# PCB_Project_Demo.net
KiCad netlist of a schematic drawn in Altium Designer
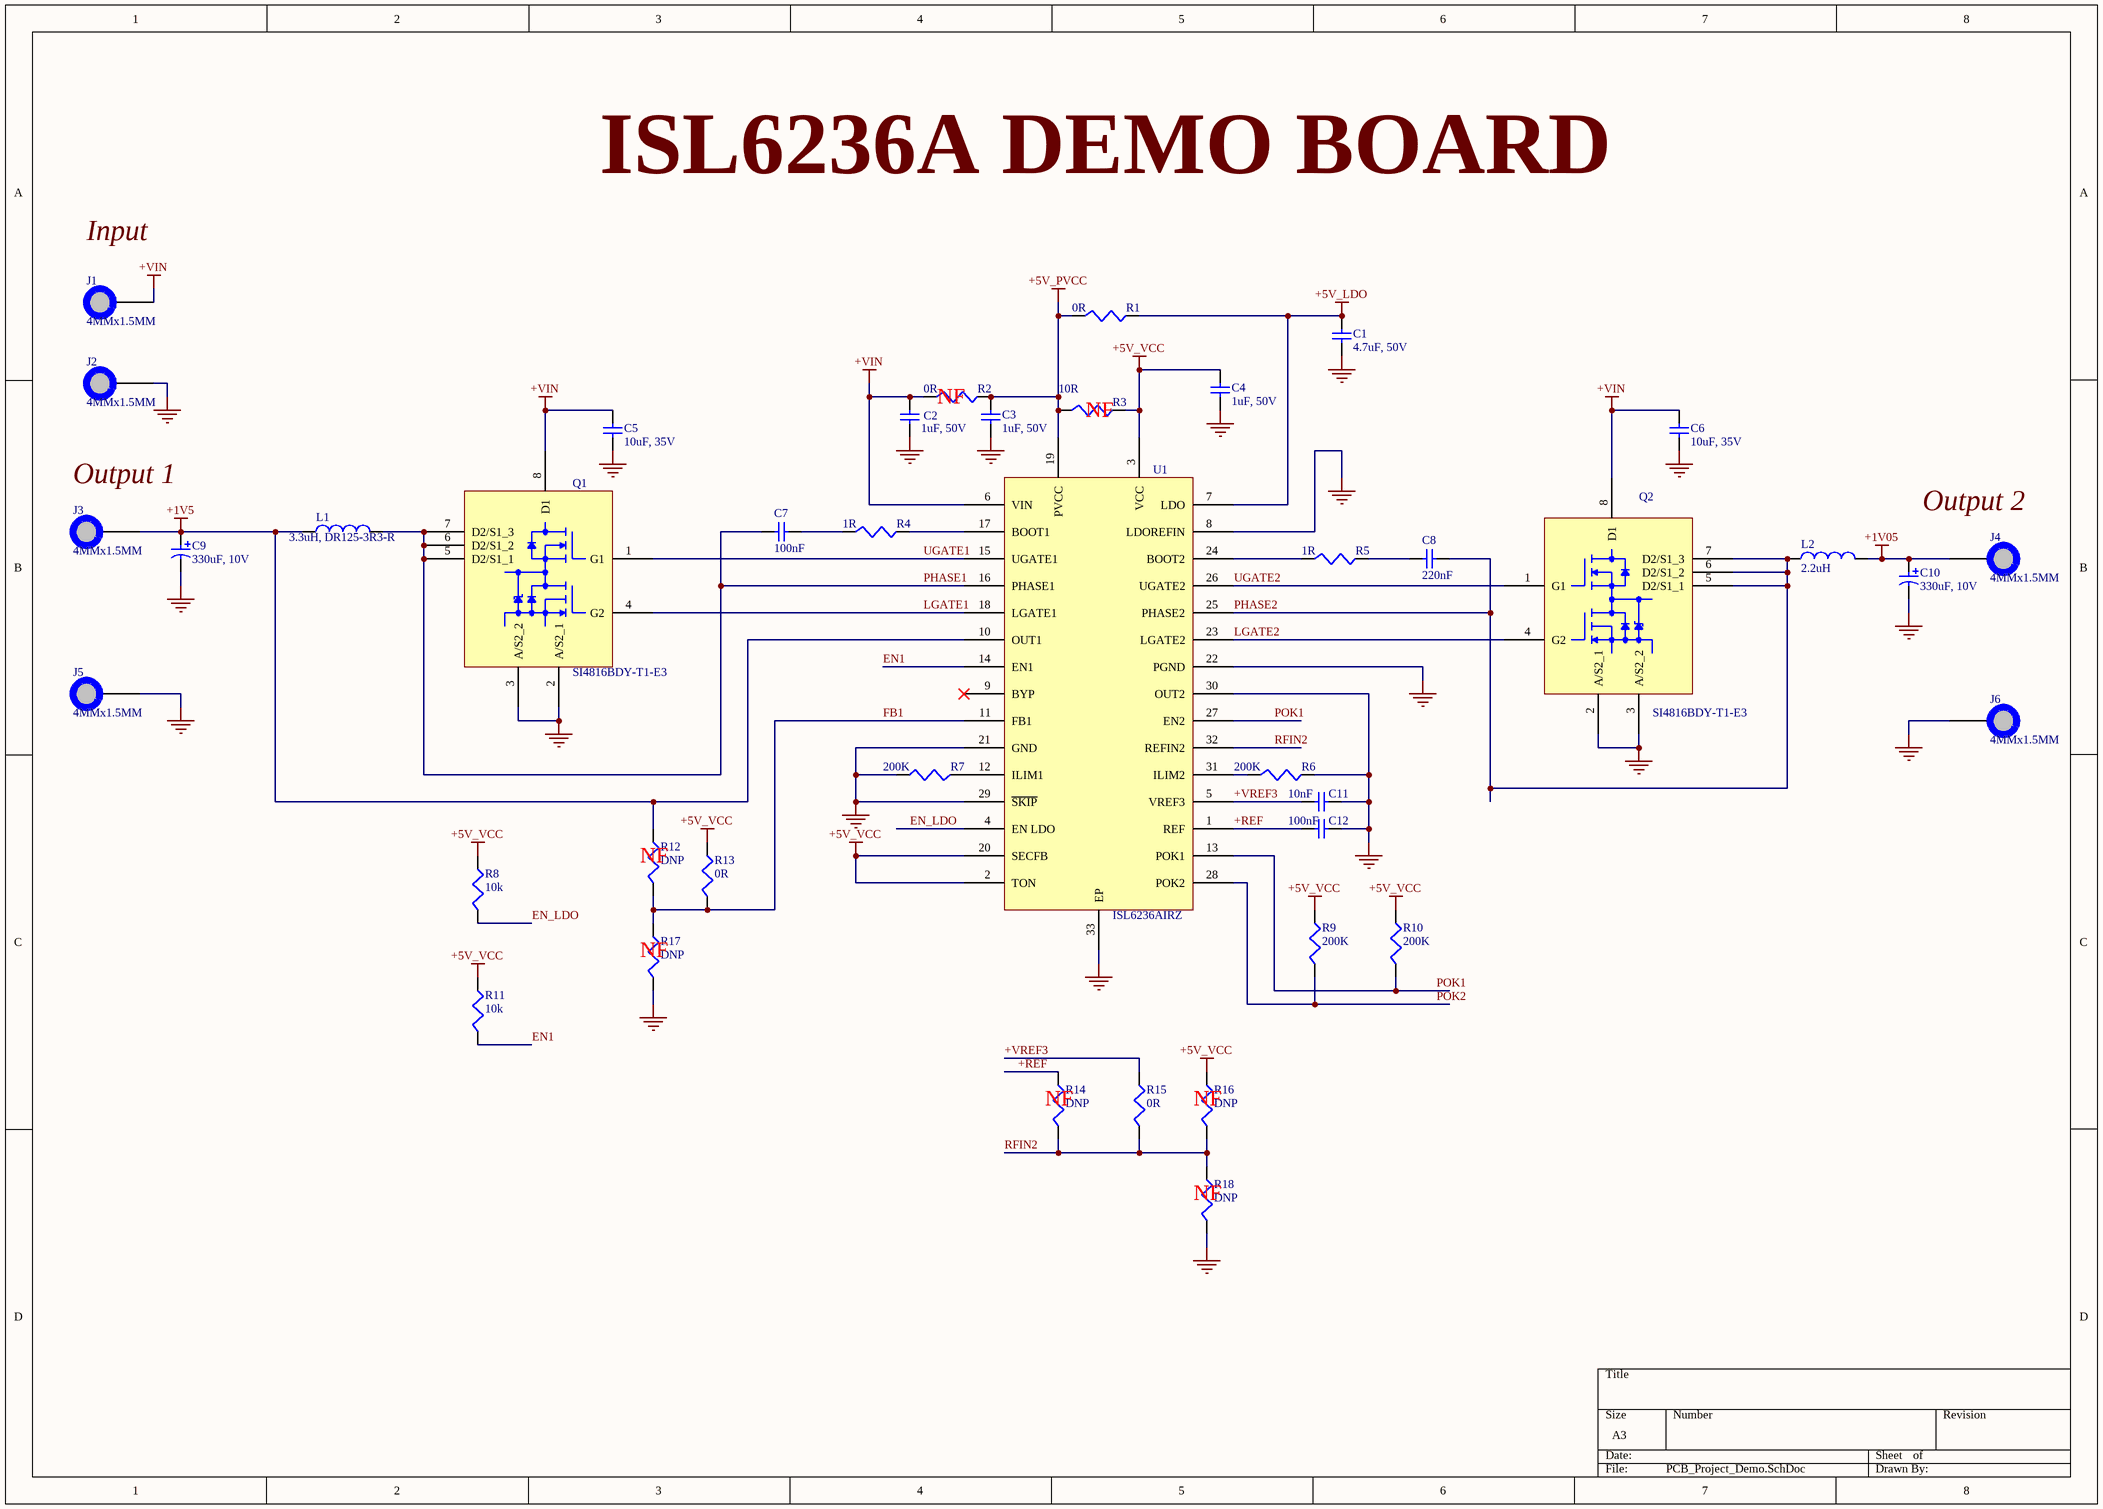
[diagram p0: PCB_Project_Demo.SchDoc]

(export (version "E")
  (design (tool "Eeschema 10.0.6"))
  (components
    (comp (ref "C1")
      (value "4.7uF, 50V")
      (footprint "C1206")
      (fields
        (field (name "MANUFACTURER") "TDK")
        (field (name "MANUFACTURER PART NUMBER") "C3216X5R1H475K160AB")
      )
      (libsource (lib "PCB_Project_Demo") (part "C3216X5R1H475K160AB"))
    )
    (comp (ref "C2")
      (value "1uF, 50V")
      (footprint "C0805")
      (fields
        (field (name "MANUFACTURER") "KEMET")
        (field (name "MANUFACTURER PART NUMBER") "C0805C105K5RACTU")
      )
      (libsource (lib "PCB_Project_Demo") (part "C0805C105K5RACTU (2)"))
    )
    (comp (ref "C3")
      (value "1uF, 50V")
      (footprint "C0805")
      (fields
        (field (name "MANUFACTURER") "KEMET")
        (field (name "MANUFACTURER PART NUMBER") "C0805C105K5RACTU")
      )
      (libsource (lib "PCB_Project_Demo") (part "C0805C105K5RACTU (2)"))
    )
    (comp (ref "C4")
      (value "1uF, 50V")
      (footprint "C0805")
      (fields
        (field (name "MANUFACTURER") "KEMET")
        (field (name "MANUFACTURER PART NUMBER") "C0805C105K5RACTU")
      )
      (libsource (lib "PCB_Project_Demo") (part "C0805C105K5RACTU (2)"))
    )
    (comp (ref "C5")
      (value "10uF, 35V")
      (footprint "C1210")
      (fields
        (field (name "MANUFACTURER") "KEMET")
        (field (name "MANUFACTURER PART NUMBER") "C1210C106K6PACTU")
      )
      (libsource (lib "PCB_Project_Demo") (part "C1210C106K6PACTU"))
    )
    (comp (ref "C6")
      (value "10uF, 35V")
      (footprint "C1210")
      (fields
        (field (name "MANUFACTURER") "KEMET")
        (field (name "MANUFACTURER PART NUMBER") "C1210C106K6PACTU")
      )
      (libsource (lib "PCB_Project_Demo") (part "C1210C106K6PACTU"))
    )
    (comp (ref "C7")
      (value "100nF")
      (footprint "C0805")
      (description "Multilayer Ceramic Capacitor, 0.1 uF, 50 V, ± 10%, X7R, 0805 [2012 Metric]")
      (fields
        (field (name "MANUFACTURER") "KEMET")
        (field (name "MANUFACTURER PART NUMBER") "C0805C104K5RAC7800")
      )
      (libsource (lib "PCB_Project_Demo") (part "C0805C104K5RAC7800"))
    )
    (comp (ref "C8")
      (value "220nF")
      (footprint "C0805")
      (fields
        (field (name "MANUFACTURER") "KEMET")
        (field (name "MANUFACTURER PART NUMBER") "C0805C224K5RACTU")
      )
      (libsource (lib "PCB_Project_Demo") (part "C0805C224K5RACTU"))
    )
    (comp (ref "C9")
      (value "330uF, 10V")
      (footprint "7343-43")
      (fields
        (field (name "MANUFACTURER") "KEMET")
        (field (name "MANUFACTURER PART NUMBER") "T530X337M010ATE004")
      )
      (libsource (lib "PCB_Project_Demo") (part "T530X337M010ATE004"))
    )
    (comp (ref "C10")
      (value "330uF, 10V")
      (footprint "7343-43")
      (fields
        (field (name "MANUFACTURER") "KEMET")
        (field (name "MANUFACTURER PART NUMBER") "T530X337M010ATE004")
      )
      (libsource (lib "PCB_Project_Demo") (part "T530X337M010ATE004"))
    )
    (comp (ref "C11")
      (value "10nF")
      (footprint "C0805")
      (description "Ceramic Capacitor, Ceramic, 50V, 10% +Tol, 10% -Tol, X7R, -/+15ppm/Cel TC, 0.01uF, 0805")
      (fields
        (field (name "MANUFACTURER") "KEMET")
        (field (name "MANUFACTURER PART NUMBER") "C0805F103K5RACTU")
      )
      (libsource (lib "PCB_Project_Demo") (part "C0805F103K5RACTU"))
    )
    (comp (ref "C12")
      (value "100nF")
      (footprint "C0805")
      (description "Multilayer Ceramic Capacitor, 0.1 uF, 50 V, ± 10%, X7R, 0805 [2012 Metric]")
      (fields
        (field (name "MANUFACTURER") "KEMET")
        (field (name "MANUFACTURER PART NUMBER") "C0805C104K5RAC7800")
      )
      (libsource (lib "PCB_Project_Demo") (part "C0805C104K5RAC7800"))
    )
    (comp (ref "J1")
      (value "4MMx1.5MM")
      (footprint "PAD_WITH_HOLE_4MMx1MM5")
      (description "Pad with a hole 4mm x 1.5mm")
      (libsource (lib "PCB_Project_Demo") (part "PAD_WITH_HOLE_4MMx1MM5"))
    )
    (comp (ref "J2")
      (value "4MMx1.5MM")
      (footprint "PAD_WITH_HOLE_4MMx1MM5")
      (description "Pad with a hole 4mm x 1.5mm")
      (libsource (lib "PCB_Project_Demo") (part "PAD_WITH_HOLE_4MMx1MM5"))
    )
    (comp (ref "J3")
      (value "4MMx1.5MM")
      (footprint "PAD_WITH_HOLE_4MMx1MM5")
      (description "Pad with a hole 4mm x 1.5mm")
      (libsource (lib "PCB_Project_Demo") (part "PAD_WITH_HOLE_4MMx1MM5"))
    )
    (comp (ref "J4")
      (value "4MMx1.5MM")
      (footprint "PAD_WITH_HOLE_4MMx1MM5")
      (description "Pad with a hole 4mm x 1.5mm")
      (libsource (lib "PCB_Project_Demo") (part "PAD_WITH_HOLE_4MMx1MM5"))
    )
    (comp (ref "J5")
      (value "4MMx1.5MM")
      (footprint "PAD_WITH_HOLE_4MMx1MM5")
      (description "Pad with a hole 4mm x 1.5mm")
      (libsource (lib "PCB_Project_Demo") (part "PAD_WITH_HOLE_4MMx1MM5"))
    )
    (comp (ref "J6")
      (value "4MMx1.5MM")
      (footprint "PAD_WITH_HOLE_4MMx1MM5")
      (description "Pad with a hole 4mm x 1.5mm")
      (libsource (lib "PCB_Project_Demo") (part "PAD_WITH_HOLE_4MMx1MM5"))
    )
    (comp (ref "L1")
      (value "3.3uH, DR125-3R3-R")
      (footprint "DR125")
      (description "Inductor Power Shielded Drum Core 3.3uH 20% 100KHz Ferrite 9.26A 6.3mOhm DCR T/R")
      (fields
        (field (name "MANUFACTURER") "Eaton Cooper")
        (field (name "MANUFACTURER PART NUMBER") "DR125-3R3-R")
      )
      (libsource (lib "PCB_Project_Demo") (part "DR125-3R3-R"))
    )
    (comp (ref "L2")
      (value "2.2uH")
      (footprint "DR125")
      (description "General Purpose Inductor, 2.2uH, 20%, 1 Element, Ferrite-Core, SMD, 4949")
      (fields
        (field (name "MANUFACTURER") "Eaton Cooper")
        (field (name "MANUFACTURER PART NUMBER") "DR125-2R2-R")
      )
      (libsource (lib "PCB_Project_Demo") (part "DR125-2R2-R"))
    )
    (comp (ref "Q1")
      (value "SI4816BDY-T1-E3")
      (footprint "SO-8")
      (fields (field (name "MANUFACTURER") "Vishay Siliconix"))
      (libsource (lib "PCB_Project_Demo") (part "SI4816BDY-T1-E3"))
    )
    (comp (ref "Q2")
      (value "SI4816BDY-T1-E3")
      (footprint "SO-8")
      (fields (field (name "MANUFACTURER") "Vishay Siliconix"))
      (libsource (lib "") (part "SI4816BDY-T1-E3_1"))
    )
    (comp (ref "R1")
      (value "0R")
      (footprint "R0805")
      (description "Fixed Resistor, Metal Glaze/thick Film, 0.125W, 0ohm, Surface Mount, 0805")
      (fields
        (field (name "MANUFACTURER") "Yageo")
        (field (name "MANUFACTURER PART NUMBER") "AC0805JR-070RL")
      )
      (libsource (lib "PCB_Project_Demo") (part "AC0805JR-070RL"))
    )
    (comp (ref "R2")
      (value "0R")
      (footprint "R0805")
      (description "Fixed Resistor, Metal Glaze/thick Film, 0.125W, 0ohm, Surface Mount, 0805")
      (fields
        (field (name "MANUFACTURER") "Yageo")
        (field (name "MANUFACTURER PART NUMBER") "AC0805JR-070RL")
      )
      (libsource (lib "PCB_Project_Demo") (part "AC0805JR-070RL"))
    )
    (comp (ref "R3")
      (value "10R")
      (footprint "R0805")
      (fields
        (field (name "MANUFACTURER") "Yageo")
        (field (name "MANUFACTURER PART NUMBER") "AC0805FR-0710RL")
        (field (name "TOLERANCE") "1%")
      )
      (libsource (lib "PCB_Project_Demo") (part "AC0805FR-0710RL"))
    )
    (comp (ref "R4")
      (value "1R")
      (footprint "R0805")
      (fields
        (field (name "MANUFACTURER") "Yageo")
        (field (name "MANUFACTURER PART NUMBER") "AC0805FR-071RL")
        (field (name "TOLERANCE") "1%")
      )
      (libsource (lib "PCB_Project_Demo") (part "AC0805FR-071RL"))
    )
    (comp (ref "R5")
      (value "1R")
      (footprint "R0805")
      (fields
        (field (name "MANUFACTURER") "Yageo")
        (field (name "MANUFACTURER PART NUMBER") "AC0805FR-071RL")
        (field (name "TOLERANCE") "1%")
      )
      (libsource (lib "PCB_Project_Demo") (part "AC0805FR-071RL"))
    )
    (comp (ref "R6")
      (value "200K")
      (footprint "R0805")
      (fields
        (field (name "MANUFACTURER") "Yageo")
        (field (name "MANUFACTURER PART NUMBER") "AC0805FR-07200KL")
        (field (name "TOLERANCE") "1%")
      )
      (libsource (lib "PCB_Project_Demo") (part "AC0805FR-07200KL"))
    )
    (comp (ref "R7")
      (value "200K")
      (footprint "R0805")
      (fields
        (field (name "MANUFACTURER") "Yageo")
        (field (name "MANUFACTURER PART NUMBER") "AC0805FR-07200KL")
        (field (name "TOLERANCE") "1%")
      )
      (libsource (lib "PCB_Project_Demo") (part "AC0805FR-07200KL"))
    )
    (comp (ref "R8")
      (value "10k")
      (footprint "R0805")
      (fields
        (field (name "MANUFACTURER") "Yageo")
        (field (name "MANUFACTURER PART NUMBER") "AC0805FR-0710KL")
        (field (name "TOLERANCE") "1%")
      )
      (libsource (lib "PCB_Project_Demo") (part "AC0805FR-0710KL"))
    )
    (comp (ref "R9")
      (value "200K")
      (footprint "R0805")
      (fields
        (field (name "MANUFACTURER") "Yageo")
        (field (name "MANUFACTURER PART NUMBER") "AC0805FR-07200KL")
        (field (name "TOLERANCE") "1%")
      )
      (libsource (lib "PCB_Project_Demo") (part "AC0805FR-07200KL"))
    )
    (comp (ref "R10")
      (value "200K")
      (footprint "R0805")
      (fields
        (field (name "MANUFACTURER") "Yageo")
        (field (name "MANUFACTURER PART NUMBER") "AC0805FR-07200KL")
        (field (name "TOLERANCE") "1%")
      )
      (libsource (lib "PCB_Project_Demo") (part "AC0805FR-07200KL"))
    )
    (comp (ref "R11")
      (value "10k")
      (footprint "R0805")
      (fields
        (field (name "MANUFACTURER") "Yageo")
        (field (name "MANUFACTURER PART NUMBER") "AC0805FR-0710KL")
        (field (name "TOLERANCE") "1%")
      )
      (libsource (lib "PCB_Project_Demo") (part "AC0805FR-0710KL"))
    )
    (comp (ref "R12") (value "DNP") (footprint "R0805") (libsource (lib "PCB_Project_Demo") (part "RES")))
    (comp (ref "R13")
      (value "0R")
      (footprint "R0805")
      (description "Fixed Resistor, Metal Glaze/thick Film, 0.125W, 0ohm, Surface Mount, 0805")
      (fields
        (field (name "MANUFACTURER") "Yageo")
        (field (name "MANUFACTURER PART NUMBER") "AC0805JR-070RL")
      )
      (libsource (lib "PCB_Project_Demo") (part "AC0805JR-070RL"))
    )
    (comp (ref "R14") (value "DNP") (footprint "R0805") (libsource (lib "PCB_Project_Demo") (part "RES")))
    (comp (ref "R15")
      (value "0R")
      (footprint "R0805")
      (description "Fixed Resistor, Metal Glaze/thick Film, 0.125W, 0ohm, Surface Mount, 0805")
      (fields
        (field (name "MANUFACTURER") "Yageo")
        (field (name "MANUFACTURER PART NUMBER") "AC0805JR-070RL")
      )
      (libsource (lib "PCB_Project_Demo") (part "AC0805JR-070RL"))
    )
    (comp (ref "R16") (value "DNP") (footprint "R0805") (libsource (lib "PCB_Project_Demo") (part "RES")))
    (comp (ref "R17") (value "DNP") (footprint "R0805") (libsource (lib "PCB_Project_Demo") (part "RES")))
    (comp (ref "R18") (value "DNP") (footprint "R0805") (libsource (lib "PCB_Project_Demo") (part "RES")))
    (comp (ref "U1")
      (value "ISL6236AIRZ")
      (footprint "L32.5x5B")
      (description "Dual Switching Controller, Current-mode, 500kHz Switching Freq-Max, BICMOS, PQCC32")
      (fields (field (name "MANUFACTURER") "Renesas"))
      (libsource (lib "PCB_Project_Demo") (part "ISL6236AIRZ"))
    )
  )
  (nets
    (net (code "1") (name "+1V5") (class "Default")
      (node (ref "C9") (pin "1") (pinfunction "1_1") (pintype "passive"))
      (node (ref "J3") (pin "1") (pinfunction "1_1") (pintype "passive"))
      (node (ref "L1") (pin "1") (pinfunction "1_1") (pintype "passive"))
      (node (ref "R12") (pin "2") (pinfunction "2_2") (pintype "passive"))
      (node (ref "U1") (pin "10") (pinfunction "OUT1_10") (pintype "passive"))
    )
    (net (code "2") (name "+1V05") (class "Default")
      (node (ref "C10") (pin "1") (pinfunction "1_1") (pintype "passive"))
      (node (ref "J4") (pin "1") (pinfunction "1_1") (pintype "passive"))
      (node (ref "L2") (pin "2") (pinfunction "2_2") (pintype "passive"))
    )
    (net (code "3") (name "+5V_LDO") (class "Default")
      (node (ref "C1") (pin "2") (pinfunction "2_2") (pintype "passive"))
      (node (ref "R1") (pin "2") (pinfunction "2_2") (pintype "passive"))
      (node (ref "U1") (pin "7") (pinfunction "LDO_7") (pintype "passive"))
    )
    (net (code "4") (name "+5V_PVCC") (class "Default")
      (node (ref "C3") (pin "2") (pinfunction "2_2") (pintype "passive"))
      (node (ref "R1") (pin "1") (pinfunction "1_1") (pintype "passive"))
      (node (ref "R2") (pin "2") (pinfunction "2_2") (pintype "passive"))
      (node (ref "R3") (pin "1") (pinfunction "1_1") (pintype "passive"))
      (node (ref "U1") (pin "19") (pinfunction "PVCC_19") (pintype "passive"))
    )
    (net (code "5") (name "+5V_VCC") (class "Default")
      (node (ref "C4") (pin "2") (pinfunction "2_2") (pintype "passive"))
      (node (ref "R10") (pin "2") (pinfunction "2_2") (pintype "passive"))
      (node (ref "R11") (pin "2") (pinfunction "2_2") (pintype "passive"))
      (node (ref "R13") (pin "2") (pinfunction "2_2") (pintype "passive"))
      (node (ref "R16") (pin "2") (pinfunction "2_2") (pintype "passive"))
      (node (ref "R3") (pin "2") (pinfunction "2_2") (pintype "passive"))
      (node (ref "R8") (pin "2") (pinfunction "2_2") (pintype "passive"))
      (node (ref "R9") (pin "2") (pinfunction "2_2") (pintype "passive"))
      (node (ref "U1") (pin "2") (pinfunction "TON_2") (pintype "passive"))
      (node (ref "U1") (pin "20") (pinfunction "SECFB_20") (pintype "passive"))
      (node (ref "U1") (pin "3") (pinfunction "VCC_3") (pintype "passive"))
    )
    (net (code "6") (name "+VIN") (class "Default")
      (node (ref "C2") (pin "2") (pinfunction "2_2") (pintype "passive"))
      (node (ref "C5") (pin "2") (pinfunction "2_2") (pintype "passive"))
      (node (ref "C6") (pin "2") (pinfunction "2_2") (pintype "passive"))
      (node (ref "J1") (pin "1") (pinfunction "1_1") (pintype "passive"))
      (node (ref "Q1") (pin "8") (pinfunction "D1_8") (pintype "passive"))
      (node (ref "Q2") (pin "8") (pinfunction "D1_8") (pintype "passive"))
      (node (ref "R2") (pin "1") (pinfunction "1_1") (pintype "passive"))
      (node (ref "U1") (pin "6") (pinfunction "VIN_6") (pintype "passive"))
    )
    (net (code "7") (name "/+REF") (class "Default")
      (node (ref "C12") (pin "1") (pinfunction "1_1") (pintype "passive"))
      (node (ref "R14") (pin "2") (pinfunction "2_2") (pintype "passive"))
      (node (ref "U1") (pin "1") (pinfunction "REF_1") (pintype "passive"))
    )
    (net (code "8") (name "/+VREF3") (class "Default")
      (node (ref "C11") (pin "1") (pinfunction "1_1") (pintype "passive"))
      (node (ref "R15") (pin "2") (pinfunction "2_2") (pintype "passive"))
      (node (ref "U1") (pin "5") (pinfunction "VREF3_5") (pintype "passive"))
    )
    (net (code "9") (name "/EN1") (class "Default")
      (node (ref "R11") (pin "1") (pinfunction "1_1") (pintype "passive"))
      (node (ref "U1") (pin "14") (pinfunction "EN1_14") (pintype "passive"))
    )
    (net (code "10") (name "/EN_LDO") (class "Default")
      (node (ref "R8") (pin "1") (pinfunction "1_1") (pintype "passive"))
      (node (ref "U1") (pin "4") (pinfunction "EN_LDO_4") (pintype "passive"))
    )
    (net (code "11") (name "/FB1") (class "Default")
      (node (ref "R12") (pin "1") (pinfunction "1_1") (pintype "passive"))
      (node (ref "R13") (pin "1") (pinfunction "1_1") (pintype "passive"))
      (node (ref "R17") (pin "2") (pinfunction "2_2") (pintype "passive"))
      (node (ref "U1") (pin "11") (pinfunction "FB1_11") (pintype "passive"))
    )
    (net (code "12") (name "/LGATE1") (class "Default")
      (node (ref "Q1") (pin "4") (pinfunction "G2_4") (pintype "passive"))
      (node (ref "U1") (pin "18") (pinfunction "LGATE1_18") (pintype "passive"))
    )
    (net (code "13") (name "/LGATE2") (class "Default")
      (node (ref "Q2") (pin "4") (pinfunction "G2_4") (pintype "passive"))
      (node (ref "U1") (pin "23") (pinfunction "LGATE2_23") (pintype "passive"))
    )
    (net (code "14") (name "/PHASE1") (class "Default")
      (node (ref "C7") (pin "1") (pinfunction "1_1") (pintype "passive"))
      (node (ref "L1") (pin "2") (pinfunction "2_2") (pintype "passive"))
      (node (ref "Q1") (pin "5") (pinfunction "D2/S1_1_5") (pintype "passive"))
      (node (ref "Q1") (pin "6") (pinfunction "D2/S1_2_6") (pintype "passive"))
      (node (ref "Q1") (pin "7") (pinfunction "D2/S1_3_7") (pintype "passive"))
      (node (ref "U1") (pin "16") (pinfunction "PHASE1_16") (pintype "passive"))
    )
    (net (code "15") (name "/PHASE2") (class "Default")
      (node (ref "C8") (pin "2") (pinfunction "2_2") (pintype "passive"))
      (node (ref "L2") (pin "1") (pinfunction "1_1") (pintype "passive"))
      (node (ref "Q2") (pin "5") (pinfunction "D2/S1_1_5") (pintype "passive"))
      (node (ref "Q2") (pin "6") (pinfunction "D2/S1_2_6") (pintype "passive"))
      (node (ref "Q2") (pin "7") (pinfunction "D2/S1_3_7") (pintype "passive"))
      (node (ref "U1") (pin "25") (pinfunction "PHASE2_25") (pintype "passive"))
    )
    (net (code "16") (name "/POK1") (class "Default")
      (node (ref "R10") (pin "1") (pinfunction "1_1") (pintype "passive"))
      (node (ref "U1") (pin "13") (pinfunction "POK1_13") (pintype "passive"))
      (node (ref "U1") (pin "27") (pinfunction "EN2_27") (pintype "passive"))
    )
    (net (code "17") (name "/POK2") (class "Default")
      (node (ref "R9") (pin "1") (pinfunction "1_1") (pintype "passive"))
      (node (ref "U1") (pin "28") (pinfunction "POK2_28") (pintype "passive"))
    )
    (net (code "18") (name "/RFIN2") (class "Default")
      (node (ref "R14") (pin "1") (pinfunction "1_1") (pintype "passive"))
      (node (ref "R15") (pin "1") (pinfunction "1_1") (pintype "passive"))
      (node (ref "R16") (pin "1") (pinfunction "1_1") (pintype "passive"))
      (node (ref "R18") (pin "2") (pinfunction "2_2") (pintype "passive"))
      (node (ref "U1") (pin "32") (pinfunction "REFIN2_32") (pintype "passive"))
    )
    (net (code "19") (name "/UGATE1") (class "Default")
      (node (ref "Q1") (pin "1") (pinfunction "G1_1") (pintype "passive"))
      (node (ref "U1") (pin "15") (pinfunction "UGATE1_15") (pintype "passive"))
    )
    (net (code "20") (name "/UGATE2") (class "Default")
      (node (ref "Q2") (pin "1") (pinfunction "G1_1") (pintype "passive"))
      (node (ref "U1") (pin "26") (pinfunction "UGATE2_26") (pintype "passive"))
    )
    (net (code "21") (name "GND") (class "Default")
      (node (ref "C1") (pin "1") (pinfunction "1_1") (pintype "passive"))
      (node (ref "C10") (pin "2") (pinfunction "2_2") (pintype "passive"))
      (node (ref "C11") (pin "2") (pinfunction "2_2") (pintype "passive"))
      (node (ref "C12") (pin "2") (pinfunction "2_2") (pintype "passive"))
      (node (ref "C2") (pin "1") (pinfunction "1_1") (pintype "passive"))
      (node (ref "C3") (pin "1") (pinfunction "1_1") (pintype "passive"))
      (node (ref "C4") (pin "1") (pinfunction "1_1") (pintype "passive"))
      (node (ref "C5") (pin "1") (pinfunction "1_1") (pintype "passive"))
      (node (ref "C6") (pin "1") (pinfunction "1_1") (pintype "passive"))
      (node (ref "C9") (pin "2") (pinfunction "2_2") (pintype "passive"))
      (node (ref "J2") (pin "1") (pinfunction "1_1") (pintype "passive"))
      (node (ref "J5") (pin "1") (pinfunction "1_1") (pintype "passive"))
      (node (ref "J6") (pin "1") (pinfunction "1_1") (pintype "passive"))
      (node (ref "Q1") (pin "2") (pinfunction "A/S2_1_2") (pintype "passive"))
      (node (ref "Q1") (pin "3") (pinfunction "A/S2_2_3") (pintype "passive"))
      (node (ref "Q2") (pin "2") (pinfunction "A/S2_1_2") (pintype "passive"))
      (node (ref "Q2") (pin "3") (pinfunction "A/S2_2_3") (pintype "passive"))
      (node (ref "R17") (pin "1") (pinfunction "1_1") (pintype "passive"))
      (node (ref "R18") (pin "1") (pinfunction "1_1") (pintype "passive"))
      (node (ref "R6") (pin "2") (pinfunction "2_2") (pintype "passive"))
      (node (ref "R7") (pin "2") (pinfunction "2_2") (pintype "passive"))
      (node (ref "U1") (pin "21") (pinfunction "GND_21") (pintype "passive"))
      (node (ref "U1") (pin "22") (pinfunction "PGND_22") (pintype "passive"))
      (node (ref "U1") (pin "29") (pinfunction "~{SKIP}_29") (pintype "passive"))
      (node (ref "U1") (pin "30") (pinfunction "OUT2_30") (pintype "passive"))
      (node (ref "U1") (pin "33") (pinfunction "EP_33") (pintype "passive"))
      (node (ref "U1") (pin "8") (pinfunction "LDOREFIN_8") (pintype "passive"))
    )
    (net (code "22") (name "Net-(C7-Pad2)") (class "Default")
      (node (ref "C7") (pin "2") (pinfunction "2_2") (pintype "passive"))
      (node (ref "R4") (pin "1") (pinfunction "1_1") (pintype "passive"))
    )
    (net (code "23") (name "Net-(C8-Pad1)") (class "Default")
      (node (ref "C8") (pin "1") (pinfunction "1_1") (pintype "passive"))
      (node (ref "R5") (pin "2") (pinfunction "2_2") (pintype "passive"))
    )
    (net (code "24") (name "Net-(U1-BOOT1)") (class "Default")
      (node (ref "R4") (pin "2") (pinfunction "2_2") (pintype "passive"))
      (node (ref "U1") (pin "17") (pinfunction "BOOT1_17") (pintype "passive"))
    )
    (net (code "25") (name "Net-(U1-BOOT2)") (class "Default")
      (node (ref "R5") (pin "1") (pinfunction "1_1") (pintype "passive"))
      (node (ref "U1") (pin "24") (pinfunction "BOOT2_24") (pintype "passive"))
    )
    (net (code "26") (name "Net-(U1-ILIM1)") (class "Default")
      (node (ref "R7") (pin "1") (pinfunction "1_1") (pintype "passive"))
      (node (ref "U1") (pin "12") (pinfunction "ILIM1_12") (pintype "passive"))
    )
    (net (code "27") (name "Net-(U1-ILIM2)") (class "Default")
      (node (ref "R6") (pin "1") (pinfunction "1_1") (pintype "passive"))
      (node (ref "U1") (pin "31") (pinfunction "ILIM2_31") (pintype "passive"))
    )
    (net (code "28") (name "unconnected-(U1-BYP-Pad9)") (class "Default")
      (node (ref "U1") (pin "9") (pinfunction "BYP_9") (pintype "passive+no_connect"))
    )
  )
)
